# B_E-Label.net
KiCad netlist of a schematic drawn in Altium Designer
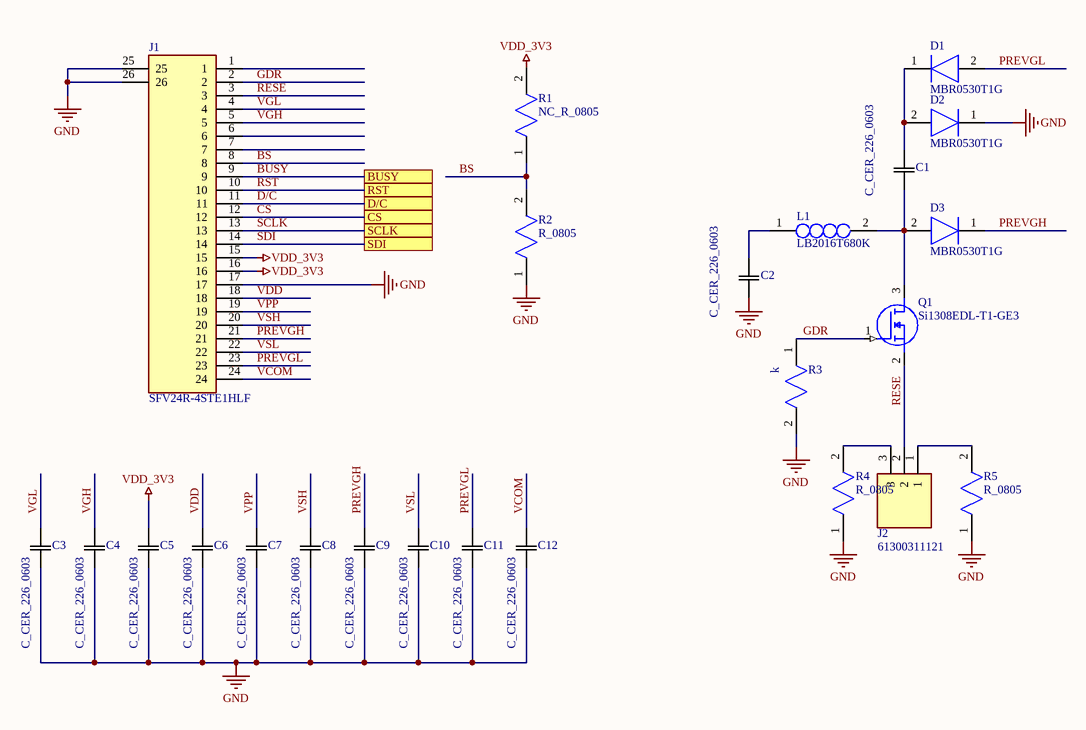
[diagram p0: B_E-Label.SchDoc]

(export (version "E")
  (design (tool "Eeschema 10.0.6"))
  (components
    (comp (ref "C1")
      (value "C_CER_226_0603")
      (footprint "CAPC1608X90N")
      (fields
        (field (name "MANUFACTURER_PART_NUMBER") "GRM188R60J226MEA0D")
        (field (name "COPYRIGHT") "Copyright (C) 2015 Accelerated Designs. All rights reserved")
      )
      (libsource (lib "Main") (part "C_CER_226_0603"))
    )
    (comp (ref "C2")
      (value "C_CER_226_0603")
      (footprint "CAPC1608X90N")
      (fields
        (field (name "MANUFACTURER_PART_NUMBER") "GRM188R60J226MEA0D")
        (field (name "COPYRIGHT") "Copyright (C) 2015 Accelerated Designs. All rights reserved")
      )
      (libsource (lib "Main") (part "C_CER_226_0603"))
    )
    (comp (ref "C3")
      (value "C_CER_226_0603")
      (footprint "CAPC1608X90N")
      (fields
        (field (name "MANUFACTURER_PART_NUMBER") "GRM188R60J226MEA0D")
        (field (name "COPYRIGHT") "Copyright (C) 2015 Accelerated Designs. All rights reserved")
      )
      (libsource (lib "Main") (part "C_CER_226_0603"))
    )
    (comp (ref "C4")
      (value "C_CER_226_0603")
      (footprint "CAPC1608X90N")
      (fields
        (field (name "MANUFACTURER_PART_NUMBER") "GRM188R60J226MEA0D")
        (field (name "COPYRIGHT") "Copyright (C) 2015 Accelerated Designs. All rights reserved")
      )
      (libsource (lib "Main") (part "C_CER_226_0603"))
    )
    (comp (ref "C5")
      (value "C_CER_226_0603")
      (footprint "CAPC1608X90N")
      (fields
        (field (name "MANUFACTURER_PART_NUMBER") "GRM188R60J226MEA0D")
        (field (name "COPYRIGHT") "Copyright (C) 2015 Accelerated Designs. All rights reserved")
      )
      (libsource (lib "Main") (part "C_CER_226_0603"))
    )
    (comp (ref "C6")
      (value "C_CER_226_0603")
      (footprint "CAPC1608X90N")
      (fields
        (field (name "MANUFACTURER_PART_NUMBER") "GRM188R60J226MEA0D")
        (field (name "COPYRIGHT") "Copyright (C) 2015 Accelerated Designs. All rights reserved")
      )
      (libsource (lib "Main") (part "C_CER_226_0603"))
    )
    (comp (ref "C7")
      (value "C_CER_226_0603")
      (footprint "CAPC1608X90N")
      (fields
        (field (name "MANUFACTURER_PART_NUMBER") "GRM188R60J226MEA0D")
        (field (name "COPYRIGHT") "Copyright (C) 2015 Accelerated Designs. All rights reserved")
      )
      (libsource (lib "Main") (part "C_CER_226_0603"))
    )
    (comp (ref "C8")
      (value "C_CER_226_0603")
      (footprint "CAPC1608X90N")
      (fields
        (field (name "MANUFACTURER_PART_NUMBER") "GRM188R60J226MEA0D")
        (field (name "COPYRIGHT") "Copyright (C) 2015 Accelerated Designs. All rights reserved")
      )
      (libsource (lib "Main") (part "C_CER_226_0603"))
    )
    (comp (ref "C9")
      (value "C_CER_226_0603")
      (footprint "CAPC1608X90N")
      (fields
        (field (name "MANUFACTURER_PART_NUMBER") "GRM188R60J226MEA0D")
        (field (name "COPYRIGHT") "Copyright (C) 2015 Accelerated Designs. All rights reserved")
      )
      (libsource (lib "Main") (part "C_CER_226_0603"))
    )
    (comp (ref "C10")
      (value "C_CER_226_0603")
      (footprint "CAPC1608X90N")
      (fields
        (field (name "MANUFACTURER_PART_NUMBER") "GRM188R60J226MEA0D")
        (field (name "COPYRIGHT") "Copyright (C) 2015 Accelerated Designs. All rights reserved")
      )
      (libsource (lib "Main") (part "C_CER_226_0603"))
    )
    (comp (ref "C11")
      (value "C_CER_226_0603")
      (footprint "CAPC1608X90N")
      (fields
        (field (name "MANUFACTURER_PART_NUMBER") "GRM188R60J226MEA0D")
        (field (name "COPYRIGHT") "Copyright (C) 2015 Accelerated Designs. All rights reserved")
      )
      (libsource (lib "Main") (part "C_CER_226_0603"))
    )
    (comp (ref "C12")
      (value "C_CER_226_0603")
      (footprint "CAPC1608X90N")
      (fields
        (field (name "MANUFACTURER_PART_NUMBER") "GRM188R60J226MEA0D")
        (field (name "COPYRIGHT") "Copyright (C) 2015 Accelerated Designs. All rights reserved")
      )
      (libsource (lib "Main") (part "C_CER_226_0603"))
    )
    (comp (ref "D1")
      (value "MBR0530T1G")
      (footprint "SamacSys:SOD3716X135N")
      (description "Diode")
      (fields (field (name "MOUSER2 PART NUMBER") "863-MBR0530T1G"))
      (libsource (lib "Main") (part "MBR0530T1G"))
    )
    (comp (ref "D2")
      (value "MBR0530T1G")
      (footprint "SamacSys:SOD3716X135N")
      (description "Diode")
      (fields (field (name "MOUSER2 PART NUMBER") "863-MBR0530T1G"))
      (libsource (lib "Main") (part "MBR0530T1G"))
    )
    (comp (ref "D3")
      (value "MBR0530T1G")
      (footprint "SamacSys:SOD3716X135N")
      (description "Diode")
      (fields (field (name "MOUSER2 PART NUMBER") "863-MBR0530T1G"))
      (libsource (lib "Main") (part "MBR0530T1G"))
    )
    (comp (ref "J1")
      (value "SFV24R-4STE1HLF")
      (footprint "SamacSys:SFV24R4STE1HLF")
      (description "Connector")
      (libsource (lib "Main") (part "SFV24R-4STE1HLF"))
    )
    (comp (ref "J2")
      (value "61300311121")
      (footprint "SamacSys:HDRV3W95P0X254_1X3_762X254X869P")
      (description "Connector")
      (fields (field (name "MOUSER2 PART NUMBER") "710-61300311121"))
      (libsource (lib "Main") (part "61300311121"))
    )
    (comp (ref "L1")
      (value "LB2016T680K")
      (footprint "SamacSys:INDC2218X180N")
      (description "Inductor")
      (libsource (lib "Main") (part "LB2016T680K"))
    )
    (comp (ref "Q1")
      (value "Si1308EDL-T1-GE3")
      (footprint "SamacSys:SOT65P210X110-3N")
      (description "MOSFET (N-Channel)")
      (fields (field (name "MOUSER2 PART NUMBER") "78-SI1308EDL-T1-GE3"))
      (libsource (lib "Main") (part "Si1308EDL-T1-GE3"))
    )
    (comp (ref "R1")
      (value "NC_R_0805")
      (footprint "RESC2012X55N")
      (description "Resistor")
      (libsource (lib "Main") (part "R_0805"))
    )
    (comp (ref "R2")
      (value "R_0805")
      (footprint "RESC2012X55N")
      (description "Resistor")
      (libsource (lib "Main") (part "R_0805"))
    )
    (comp (ref "R3")
      (value "k")
      (footprint "SamacSys:RESC1005X40N")
      (description "Resistor")
      (fields (field (name "MANUFACTURER_PART_NUMBER") "CRCW0402100KFKED"))
      (libsource (lib "Main") (part "CRCW0402100KFKED"))
    )
    (comp (ref "R4")
      (value "R_0805")
      (footprint "RESC2012X55N")
      (description "Resistor")
      (libsource (lib "Main") (part "R_0805"))
    )
    (comp (ref "R5")
      (value "R_0805")
      (footprint "RESC2012X55N")
      (description "Resistor")
      (libsource (lib "Main") (part "R_0805"))
    )
  )
  (nets
    (net (code "1") (name "/BS") (class "Default")
      (node (ref "J1") (pin "8") (pinfunction "8_8") (pintype "passive"))
      (node (ref "R1") (pin "1") (pinfunction "1_1") (pintype "passive"))
      (node (ref "R2") (pin "2") (pinfunction "2_2") (pintype "passive"))
    )
    (net (code "2") (name "/BUSY") (class "Default")
      (node (ref "J1") (pin "9") (pinfunction "9_9") (pintype "passive"))
    )
    (net (code "3") (name "/CS") (class "Default")
      (node (ref "J1") (pin "12") (pinfunction "12_12") (pintype "passive"))
    )
    (net (code "4") (name "/D{slash}C") (class "Default")
      (node (ref "J1") (pin "11") (pinfunction "11_11") (pintype "passive"))
    )
    (net (code "5") (name "/GDR") (class "Default")
      (node (ref "J1") (pin "2") (pinfunction "2_2") (pintype "passive"))
      (node (ref "Q1") (pin "1") (pinfunction "G_1") (pintype "input"))
      (node (ref "R3") (pin "1") (pinfunction "1_1") (pintype "passive"))
    )
    (net (code "6") (name "/PREVGH") (class "Default")
      (node (ref "C9") (pin "2") (pinfunction "2_2") (pintype "passive"))
      (node (ref "D3") (pin "1") (pinfunction "K_1") (pintype "passive"))
      (node (ref "J1") (pin "21") (pinfunction "21_21") (pintype "passive"))
    )
    (net (code "7") (name "/PREVGL") (class "Default")
      (node (ref "C11") (pin "2") (pinfunction "2_2") (pintype "passive"))
      (node (ref "D1") (pin "2") (pinfunction "A_2") (pintype "passive"))
      (node (ref "J1") (pin "23") (pinfunction "23_23") (pintype "passive"))
    )
    (net (code "8") (name "/RESE") (class "Default")
      (node (ref "J1") (pin "3") (pinfunction "3_3") (pintype "passive"))
      (node (ref "J2") (pin "2") (pinfunction "2_2") (pintype "passive"))
      (node (ref "Q1") (pin "2") (pinfunction "S_2") (pintype "bidirectional"))
    )
    (net (code "9") (name "/RST") (class "Default")
      (node (ref "J1") (pin "10") (pinfunction "10_10") (pintype "passive"))
    )
    (net (code "10") (name "/SCLK") (class "Default")
      (node (ref "J1") (pin "13") (pinfunction "13_13") (pintype "passive"))
    )
    (net (code "11") (name "/SDI") (class "Default")
      (node (ref "J1") (pin "14") (pinfunction "14_14") (pintype "passive"))
    )
    (net (code "12") (name "/VCOM") (class "Default")
      (node (ref "C12") (pin "2") (pinfunction "2_2") (pintype "passive"))
      (node (ref "J1") (pin "24") (pinfunction "24_24") (pintype "passive"))
    )
    (net (code "13") (name "/VDD") (class "Default")
      (node (ref "C6") (pin "2") (pinfunction "2_2") (pintype "passive"))
      (node (ref "J1") (pin "18") (pinfunction "18_18") (pintype "passive"))
    )
    (net (code "14") (name "/VGH") (class "Default")
      (node (ref "C4") (pin "2") (pinfunction "2_2") (pintype "passive"))
      (node (ref "J1") (pin "5") (pinfunction "5_5") (pintype "passive"))
    )
    (net (code "15") (name "/VGL") (class "Default")
      (node (ref "C3") (pin "2") (pinfunction "2_2") (pintype "passive"))
      (node (ref "J1") (pin "4") (pinfunction "4_4") (pintype "passive"))
    )
    (net (code "16") (name "/VPP") (class "Default")
      (node (ref "C7") (pin "2") (pinfunction "2_2") (pintype "passive"))
      (node (ref "J1") (pin "19") (pinfunction "19_19") (pintype "passive"))
    )
    (net (code "17") (name "/VSH") (class "Default")
      (node (ref "C8") (pin "2") (pinfunction "2_2") (pintype "passive"))
      (node (ref "J1") (pin "20") (pinfunction "20_20") (pintype "passive"))
    )
    (net (code "18") (name "/VSL") (class "Default")
      (node (ref "C10") (pin "2") (pinfunction "2_2") (pintype "passive"))
      (node (ref "J1") (pin "22") (pinfunction "22_22") (pintype "passive"))
    )
    (net (code "19") (name "GND") (class "Default")
      (node (ref "C10") (pin "1") (pinfunction "1_1") (pintype "passive"))
      (node (ref "C11") (pin "1") (pinfunction "1_1") (pintype "passive"))
      (node (ref "C12") (pin "1") (pinfunction "1_1") (pintype "passive"))
      (node (ref "C2") (pin "1") (pinfunction "1_1") (pintype "passive"))
      (node (ref "C3") (pin "1") (pinfunction "1_1") (pintype "passive"))
      (node (ref "C4") (pin "1") (pinfunction "1_1") (pintype "passive"))
      (node (ref "C5") (pin "1") (pinfunction "1_1") (pintype "passive"))
      (node (ref "C6") (pin "1") (pinfunction "1_1") (pintype "passive"))
      (node (ref "C7") (pin "1") (pinfunction "1_1") (pintype "passive"))
      (node (ref "C8") (pin "1") (pinfunction "1_1") (pintype "passive"))
      (node (ref "C9") (pin "1") (pinfunction "1_1") (pintype "passive"))
      (node (ref "D2") (pin "1") (pinfunction "K_1") (pintype "passive"))
      (node (ref "J1") (pin "17") (pinfunction "17_17") (pintype "passive"))
      (node (ref "J1") (pin "25") (pinfunction "25_25") (pintype "passive"))
      (node (ref "J1") (pin "26") (pinfunction "26_26") (pintype "passive"))
      (node (ref "R2") (pin "1") (pinfunction "1_1") (pintype "passive"))
      (node (ref "R3") (pin "2") (pinfunction "2_2") (pintype "passive"))
      (node (ref "R4") (pin "1") (pinfunction "1_1") (pintype "passive"))
      (node (ref "R5") (pin "1") (pinfunction "1_1") (pintype "passive"))
    )
    (net (code "20") (name "Net-(C2-Pad2)") (class "Default")
      (node (ref "C2") (pin "2") (pinfunction "2_2") (pintype "passive"))
      (node (ref "L1") (pin "1") (pinfunction "1_1") (pintype "passive"))
    )
    (net (code "21") (name "Net-(D1-K)") (class "Default")
      (node (ref "C1") (pin "2") (pinfunction "2_2") (pintype "passive"))
      (node (ref "D1") (pin "1") (pinfunction "K_1") (pintype "passive"))
      (node (ref "D2") (pin "2") (pinfunction "A_2") (pintype "passive"))
    )
    (net (code "22") (name "Net-(D3-A)") (class "Default")
      (node (ref "C1") (pin "1") (pinfunction "1_1") (pintype "passive"))
      (node (ref "D3") (pin "2") (pinfunction "A_2") (pintype "passive"))
      (node (ref "L1") (pin "2") (pinfunction "2_2") (pintype "passive"))
      (node (ref "Q1") (pin "3") (pinfunction "D_3") (pintype "bidirectional"))
    )
    (net (code "23") (name "Net-(J2-Pad1)") (class "Default")
      (node (ref "J2") (pin "1") (pinfunction "1_1") (pintype "passive"))
      (node (ref "R5") (pin "2") (pinfunction "2_2") (pintype "passive"))
    )
    (net (code "24") (name "Net-(J2-Pad3)") (class "Default")
      (node (ref "J2") (pin "3") (pinfunction "3_3") (pintype "passive"))
      (node (ref "R4") (pin "2") (pinfunction "2_2") (pintype "passive"))
    )
    (net (code "25") (name "VDD_3V3") (class "Default")
      (node (ref "C5") (pin "2") (pinfunction "2_2") (pintype "passive"))
      (node (ref "J1") (pin "15") (pinfunction "15_15") (pintype "passive"))
      (node (ref "J1") (pin "16") (pinfunction "16_16") (pintype "passive"))
      (node (ref "R1") (pin "2") (pinfunction "2_2") (pintype "passive"))
    )
    (net (code "26") (name "unconnected-(J1-Pad1)") (class "Default")
      (node (ref "J1") (pin "1") (pinfunction "1_1") (pintype "passive"))
    )
    (net (code "27") (name "unconnected-(J1-Pad6)") (class "Default")
      (node (ref "J1") (pin "6") (pinfunction "6_6") (pintype "passive"))
    )
    (net (code "28") (name "unconnected-(J1-Pad7)") (class "Default")
      (node (ref "J1") (pin "7") (pinfunction "7_7") (pintype "passive"))
    )
  )
)
